# usbtinyisp_single.net
KiCad netlist of a schematic drawn in EAGLE
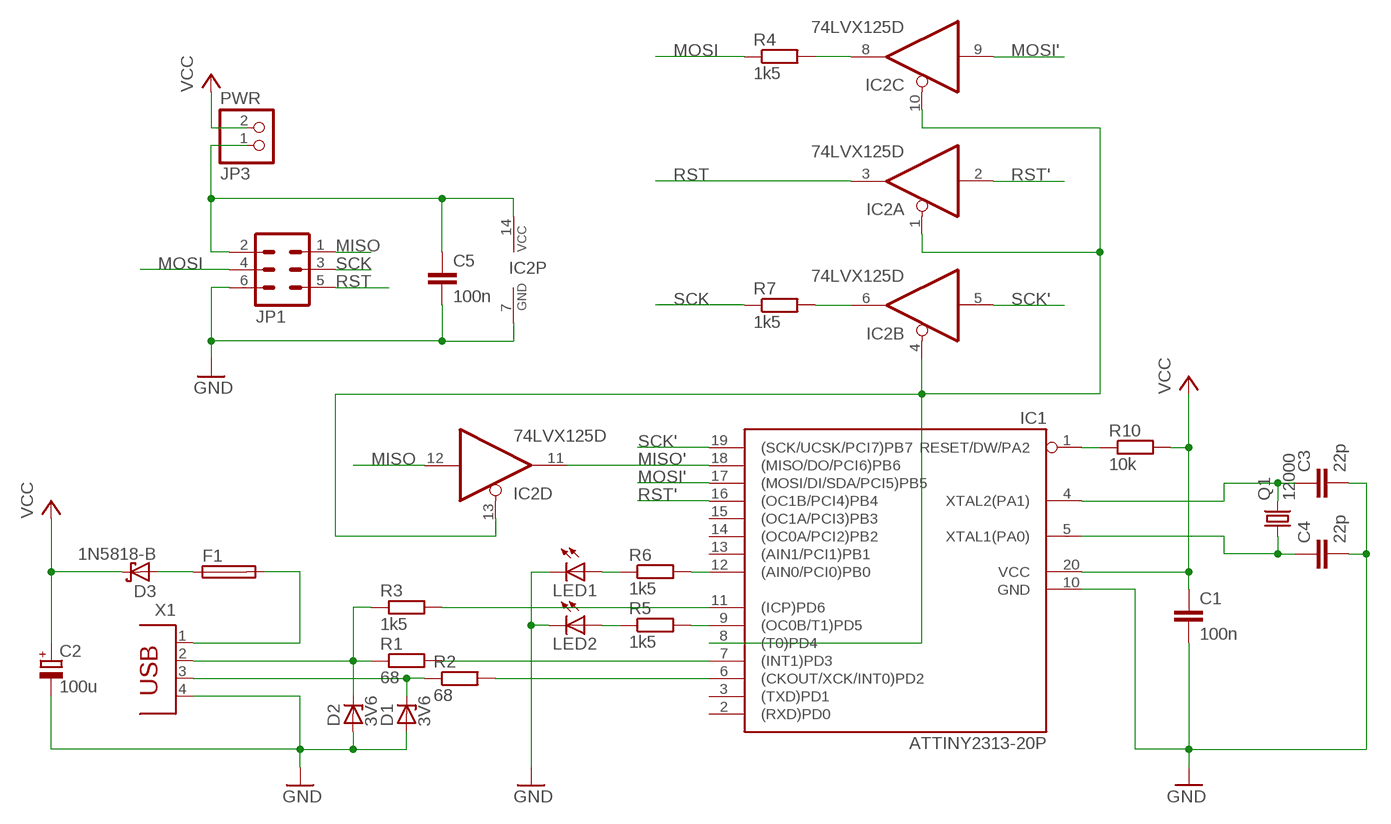
[diagram p0: schematic, sheet 1]

(export (version "E")
  (design (tool "Eeschema 10.0.6"))
  (components
    (comp (ref "C1")
      (value "100n")
      (footprint "eagle-import:C0805")
      (libsource (lib "eagle-import") (part "C-EUC0805"))
    )
    (comp (ref "C2")
      (value "100u")
      (footprint "eagle-import:E2,5-6")
      (libsource (lib "eagle-import") (part "CPOL-EUE2.5-6"))
    )
    (comp (ref "C3")
      (value "22p")
      (footprint "eagle-import:C1206")
      (libsource (lib "eagle-import") (part "C-EUC1206"))
    )
    (comp (ref "C4")
      (value "22p")
      (footprint "eagle-import:C1206")
      (libsource (lib "eagle-import") (part "C-EUC1206"))
    )
    (comp (ref "C5")
      (value "100n")
      (footprint "eagle-import:C0805")
      (libsource (lib "eagle-import") (part "C-EUC0805"))
    )
    (comp (ref "D1")
      (value "3V6")
      (footprint "eagle-import:SOD80C")
      (libsource (lib "eagle-import") (part "ZENER-DIODESOD80C"))
    )
    (comp (ref "D2")
      (value "3V6")
      (footprint "eagle-import:SOD80C")
      (libsource (lib "eagle-import") (part "ZENER-DIODESOD80C"))
    )
    (comp (ref "D3")
      (value "1N5818-B")
      (footprint "eagle-import:DO41-7.6")
      (libsource (lib "eagle-import") (part "1N5817-B"))
    )
    (comp (ref "F1")
      (value "PTC-FUSE-LP60-050")
      (footprint "eagle-import:LP60-050")
      (libsource (lib "eagle-import") (part "PTC-FUSE-LP60-050"))
    )
    (comp (ref "IC1")
      (value "ATTINY2313-20P")
      (footprint "eagle-import:DIL20")
      (libsource (lib "eagle-import") (part "ATTINY2313P-20"))
    )
    (comp (ref "IC2")
      (value "74LVX125D")
      (footprint "eagle-import:SO14")
      (libsource (lib "eagle-import") (part "74125DHC"))
    )
    (comp (ref "JP1")
      (value "ML6")
      (footprint "eagle-import:ML6")
      (libsource (lib "eagle-import") (part "ML6"))
    )
    (comp (ref "JP3")
      (value "PWR")
      (footprint "eagle-import:1X02")
      (libsource (lib "eagle-import") (part "PINHD-1X2"))
    )
    (comp (ref "LED1")
      (value "LED3MM")
      (footprint "eagle-import:LED3MM")
      (libsource (lib "eagle-import") (part "LED3MM"))
    )
    (comp (ref "LED2")
      (value "LED3MM")
      (footprint "eagle-import:LED3MM")
      (libsource (lib "eagle-import") (part "LED3MM"))
    )
    (comp (ref "Q1")
      (value "12000")
      (footprint "eagle-import:HC49U-V")
      (libsource (lib "eagle-import") (part "CRYSTALHC49U-V"))
    )
    (comp (ref "R1")
      (value "68")
      (footprint "eagle-import:0207_10")
      (libsource (lib "eagle-import") (part "R-EU_0207/10"))
    )
    (comp (ref "R2")
      (value "68")
      (footprint "eagle-import:0207_10")
      (libsource (lib "eagle-import") (part "R-EU_0207/10"))
    )
    (comp (ref "R3")
      (value "1k5")
      (footprint "eagle-import:R0805")
      (libsource (lib "eagle-import") (part "R-EU_R0805"))
    )
    (comp (ref "R4")
      (value "1k5")
      (footprint "eagle-import:R0805")
      (libsource (lib "eagle-import") (part "R-EU_R0805"))
    )
    (comp (ref "R5")
      (value "1k5")
      (footprint "eagle-import:R0805")
      (libsource (lib "eagle-import") (part "R-EU_R0805"))
    )
    (comp (ref "R6")
      (value "1k5")
      (footprint "eagle-import:R0805")
      (libsource (lib "eagle-import") (part "R-EU_R0805"))
    )
    (comp (ref "R7")
      (value "1k5")
      (footprint "eagle-import:0207_10")
      (libsource (lib "eagle-import") (part "R-EU_0207/10"))
    )
    (comp (ref "R10")
      (value "10k")
      (footprint "eagle-import:R0805")
      (libsource (lib "eagle-import") (part "R-EU_R0805"))
    )
    (comp (ref "X1")
      (value "PN61729")
      (footprint "eagle-import:PN61729")
      (libsource (lib "eagle-import") (part "PN61729"))
    )
  )
  (nets
    (net (code "1") (name "/MISO") (class "Default")
      (node (ref "IC2") (pin "12") (pinfunction "I_12") (pintype "input"))
      (node (ref "JP1") (pin "1") (pinfunction "1_1") (pintype "passive"))
    )
    (net (code "2") (name "/MISO'") (class "Default")
      (node (ref "IC1") (pin "18") (pinfunction "(MISO/DO/PCI6)PB6_18") (pintype "bidirectional"))
      (node (ref "IC2") (pin "11") (pinfunction "O_11") (pintype "tri_state"))
    )
    (net (code "3") (name "/MOSI") (class "Default")
      (node (ref "JP1") (pin "4") (pinfunction "4_4") (pintype "passive"))
      (node (ref "R4") (pin "1") (pinfunction "1_1") (pintype "passive"))
    )
    (net (code "4") (name "/MOSI'") (class "Default")
      (node (ref "IC1") (pin "17") (pinfunction "(MOSI/DI/SDA/PCI5)PB5_17") (pintype "bidirectional"))
      (node (ref "IC2") (pin "9") (pinfunction "I_9") (pintype "input"))
    )
    (net (code "5") (name "/RST") (class "Default")
      (node (ref "IC2") (pin "3") (pinfunction "O_3") (pintype "tri_state"))
      (node (ref "JP1") (pin "5") (pinfunction "5_5") (pintype "passive"))
    )
    (net (code "6") (name "/RST'") (class "Default")
      (node (ref "IC1") (pin "16") (pinfunction "(OC1B/PCI4)PB4_16") (pintype "bidirectional"))
      (node (ref "IC2") (pin "2") (pinfunction "I_2") (pintype "input"))
    )
    (net (code "7") (name "/SCK") (class "Default")
      (node (ref "JP1") (pin "3") (pinfunction "3_3") (pintype "passive"))
      (node (ref "R7") (pin "1") (pinfunction "1_1") (pintype "passive"))
    )
    (net (code "8") (name "/SCK'") (class "Default")
      (node (ref "IC1") (pin "19") (pinfunction "(SCK/UCSK/PCI7)PB7_19") (pintype "bidirectional"))
      (node (ref "IC2") (pin "5") (pinfunction "I_5") (pintype "input"))
    )
    (net (code "9") (name "GND") (class "Default")
      (node (ref "C1") (pin "2") (pinfunction "2_2") (pintype "passive"))
      (node (ref "C2") (pin "-") (pinfunction "-_-") (pintype "passive"))
      (node (ref "C3") (pin "2") (pinfunction "2_2") (pintype "passive"))
      (node (ref "C4") (pin "2") (pinfunction "2_2") (pintype "passive"))
      (node (ref "C5") (pin "2") (pinfunction "2_2") (pintype "passive"))
      (node (ref "D1") (pin "A") (pinfunction "A_A") (pintype "passive"))
      (node (ref "D2") (pin "A") (pinfunction "A_A") (pintype "passive"))
      (node (ref "IC1") (pin "10") (pinfunction "GND_10") (pintype "power_in"))
      (node (ref "IC2") (pin "7") (pinfunction "GND_7") (pintype "power_in"))
      (node (ref "JP1") (pin "6") (pinfunction "6_6") (pintype "passive"))
      (node (ref "LED1") (pin "K") (pinfunction "C_K") (pintype "passive"))
      (node (ref "LED2") (pin "K") (pinfunction "C_K") (pintype "passive"))
      (node (ref "X1") (pin "4") (pinfunction "4_4") (pintype "bidirectional"))
    )
    (net (code "10") (name "Net-(D1-PadC)") (class "Default")
      (node (ref "D1") (pin "C") (pinfunction "C_C") (pintype "passive"))
      (node (ref "R2") (pin "1") (pinfunction "1_1") (pintype "passive"))
      (node (ref "X1") (pin "3") (pinfunction "3_3") (pintype "bidirectional"))
    )
    (net (code "11") (name "Net-(D2-PadC)") (class "Default")
      (node (ref "D2") (pin "C") (pinfunction "C_C") (pintype "passive"))
      (node (ref "R1") (pin "1") (pinfunction "1_1") (pintype "passive"))
      (node (ref "R3") (pin "1") (pinfunction "1_1") (pintype "passive"))
      (node (ref "X1") (pin "2") (pinfunction "2_2") (pintype "bidirectional"))
    )
    (net (code "12") (name "Net-(F1-1)") (class "Default")
      (node (ref "D3") (pin "A") (pinfunction "A_A") (pintype "passive"))
      (node (ref "F1") (pin "P$1") (pinfunction "1_P$1") (pintype "passive"))
    )
    (net (code "13") (name "Net-(F1-2)") (class "Default")
      (node (ref "F1") (pin "P$2") (pinfunction "2_P$2") (pintype "passive"))
      (node (ref "X1") (pin "1") (pinfunction "1_1") (pintype "bidirectional"))
    )
    (net (code "14") (name "Net-(IC1-(AIN0{slash}PCI0)PB0)") (class "Default")
      (node (ref "IC1") (pin "12") (pinfunction "(AIN0/PCI0)PB0_12") (pintype "bidirectional"))
      (node (ref "R6") (pin "2") (pinfunction "2_2") (pintype "passive"))
    )
    (net (code "15") (name "Net-(IC1-(CKOUT{slash}XCK{slash}INT0)PD2)") (class "Default")
      (node (ref "IC1") (pin "6") (pinfunction "(CKOUT/XCK/INT0)PD2_6") (pintype "bidirectional"))
      (node (ref "R2") (pin "2") (pinfunction "2_2") (pintype "passive"))
    )
    (net (code "16") (name "Net-(IC1-(ICP)PD6)") (class "Default")
      (node (ref "IC1") (pin "11") (pinfunction "(ICP)PD6_11") (pintype "bidirectional"))
      (node (ref "R3") (pin "2") (pinfunction "2_2") (pintype "passive"))
    )
    (net (code "17") (name "Net-(IC1-(INT1)PD3)") (class "Default")
      (node (ref "IC1") (pin "7") (pinfunction "(INT1)PD3_7") (pintype "bidirectional"))
      (node (ref "R1") (pin "2") (pinfunction "2_2") (pintype "passive"))
    )
    (net (code "18") (name "Net-(IC1-(OC0B{slash}T1)PD5)") (class "Default")
      (node (ref "IC1") (pin "9") (pinfunction "(OC0B/T1)PD5_9") (pintype "bidirectional"))
      (node (ref "R5") (pin "2") (pinfunction "2_2") (pintype "passive"))
    )
    (net (code "19") (name "Net-(IC1-(T0)PD4)") (class "Default")
      (node (ref "IC1") (pin "8") (pinfunction "(T0)PD4_8") (pintype "bidirectional"))
      (node (ref "IC2") (pin "1") (pinfunction "OE_1") (pintype "input"))
      (node (ref "IC2") (pin "10") (pinfunction "OE_10") (pintype "input"))
      (node (ref "IC2") (pin "13") (pinfunction "OE_13") (pintype "input"))
      (node (ref "IC2") (pin "4") (pinfunction "OE_4") (pintype "input"))
    )
    (net (code "20") (name "Net-(IC1-RESET{slash}DW{slash}PA2)") (class "Default")
      (node (ref "IC1") (pin "1") (pinfunction "RESET/DW/PA2_1") (pintype "bidirectional"))
      (node (ref "R10") (pin "1") (pinfunction "1_1") (pintype "passive"))
    )
    (net (code "21") (name "Net-(IC1-XTAL1(PA0))") (class "Default")
      (node (ref "C4") (pin "1") (pinfunction "1_1") (pintype "passive"))
      (node (ref "IC1") (pin "5") (pinfunction "XTAL1(PA0)_5") (pintype "bidirectional"))
      (node (ref "Q1") (pin "1") (pinfunction "1_1") (pintype "passive"))
    )
    (net (code "22") (name "Net-(IC1-XTAL2(PA1))") (class "Default")
      (node (ref "C3") (pin "1") (pinfunction "1_1") (pintype "passive"))
      (node (ref "IC1") (pin "4") (pinfunction "XTAL2(PA1)_4") (pintype "bidirectional"))
      (node (ref "Q1") (pin "2") (pinfunction "2_2") (pintype "passive"))
    )
    (net (code "23") (name "Net-(IC2B-O)") (class "Default")
      (node (ref "IC2") (pin "6") (pinfunction "O_6") (pintype "tri_state"))
      (node (ref "R7") (pin "2") (pinfunction "2_2") (pintype "passive"))
    )
    (net (code "24") (name "Net-(IC2C-O)") (class "Default")
      (node (ref "IC2") (pin "8") (pinfunction "O_8") (pintype "tri_state"))
      (node (ref "R4") (pin "2") (pinfunction "2_2") (pintype "passive"))
    )
    (net (code "25") (name "Net-(IC2E-VCC)") (class "Default")
      (node (ref "C5") (pin "1") (pinfunction "1_1") (pintype "passive"))
      (node (ref "IC2") (pin "14") (pinfunction "VCC_14") (pintype "power_in"))
      (node (ref "JP1") (pin "2") (pinfunction "2_2") (pintype "passive"))
      (node (ref "JP3") (pin "1") (pinfunction "1_1") (pintype "passive"))
    )
    (net (code "26") (name "Net-(LED1-PadA)") (class "Default")
      (node (ref "LED1") (pin "A") (pinfunction "A_A") (pintype "passive"))
      (node (ref "R6") (pin "1") (pinfunction "1_1") (pintype "passive"))
    )
    (net (code "27") (name "Net-(LED2-PadA)") (class "Default")
      (node (ref "LED2") (pin "A") (pinfunction "A_A") (pintype "passive"))
      (node (ref "R5") (pin "1") (pinfunction "1_1") (pintype "passive"))
    )
    (net (code "28") (name "VCC") (class "Default")
      (node (ref "C1") (pin "1") (pinfunction "1_1") (pintype "passive"))
      (node (ref "C2") (pin "+") (pinfunction "+_+") (pintype "passive"))
      (node (ref "D3") (pin "C") (pinfunction "C_C") (pintype "passive"))
      (node (ref "IC1") (pin "20") (pinfunction "VCC_20") (pintype "power_in"))
      (node (ref "JP3") (pin "2") (pinfunction "2_2") (pintype "passive"))
      (node (ref "R10") (pin "2") (pinfunction "2_2") (pintype "passive"))
    )
    (net (code "29") (name "unconnected-(IC1-(AIN1{slash}PCI1)PB1-Pad13)") (class "Default")
      (node (ref "IC1") (pin "13") (pinfunction "(AIN1/PCI1)PB1_13") (pintype "bidirectional"))
    )
    (net (code "30") (name "unconnected-(IC1-(OC0A{slash}PCI2)PB2-Pad14)") (class "Default")
      (node (ref "IC1") (pin "14") (pinfunction "(OC0A/PCI2)PB2_14") (pintype "bidirectional"))
    )
    (net (code "31") (name "unconnected-(IC1-(OC1A{slash}PCI3)PB3-Pad15)") (class "Default")
      (node (ref "IC1") (pin "15") (pinfunction "(OC1A/PCI3)PB3_15") (pintype "bidirectional"))
    )
    (net (code "32") (name "unconnected-(IC1-(RXD)PD0-Pad2)") (class "Default")
      (node (ref "IC1") (pin "2") (pinfunction "(RXD)PD0_2") (pintype "bidirectional"))
    )
    (net (code "33") (name "unconnected-(IC1-(TXD)PD1-Pad3)") (class "Default")
      (node (ref "IC1") (pin "3") (pinfunction "(TXD)PD1_3") (pintype "bidirectional"))
    )
  )
)
